# VoiceRecognition_Team3.net
KiCad netlist of a schematic drawn in EAGLE
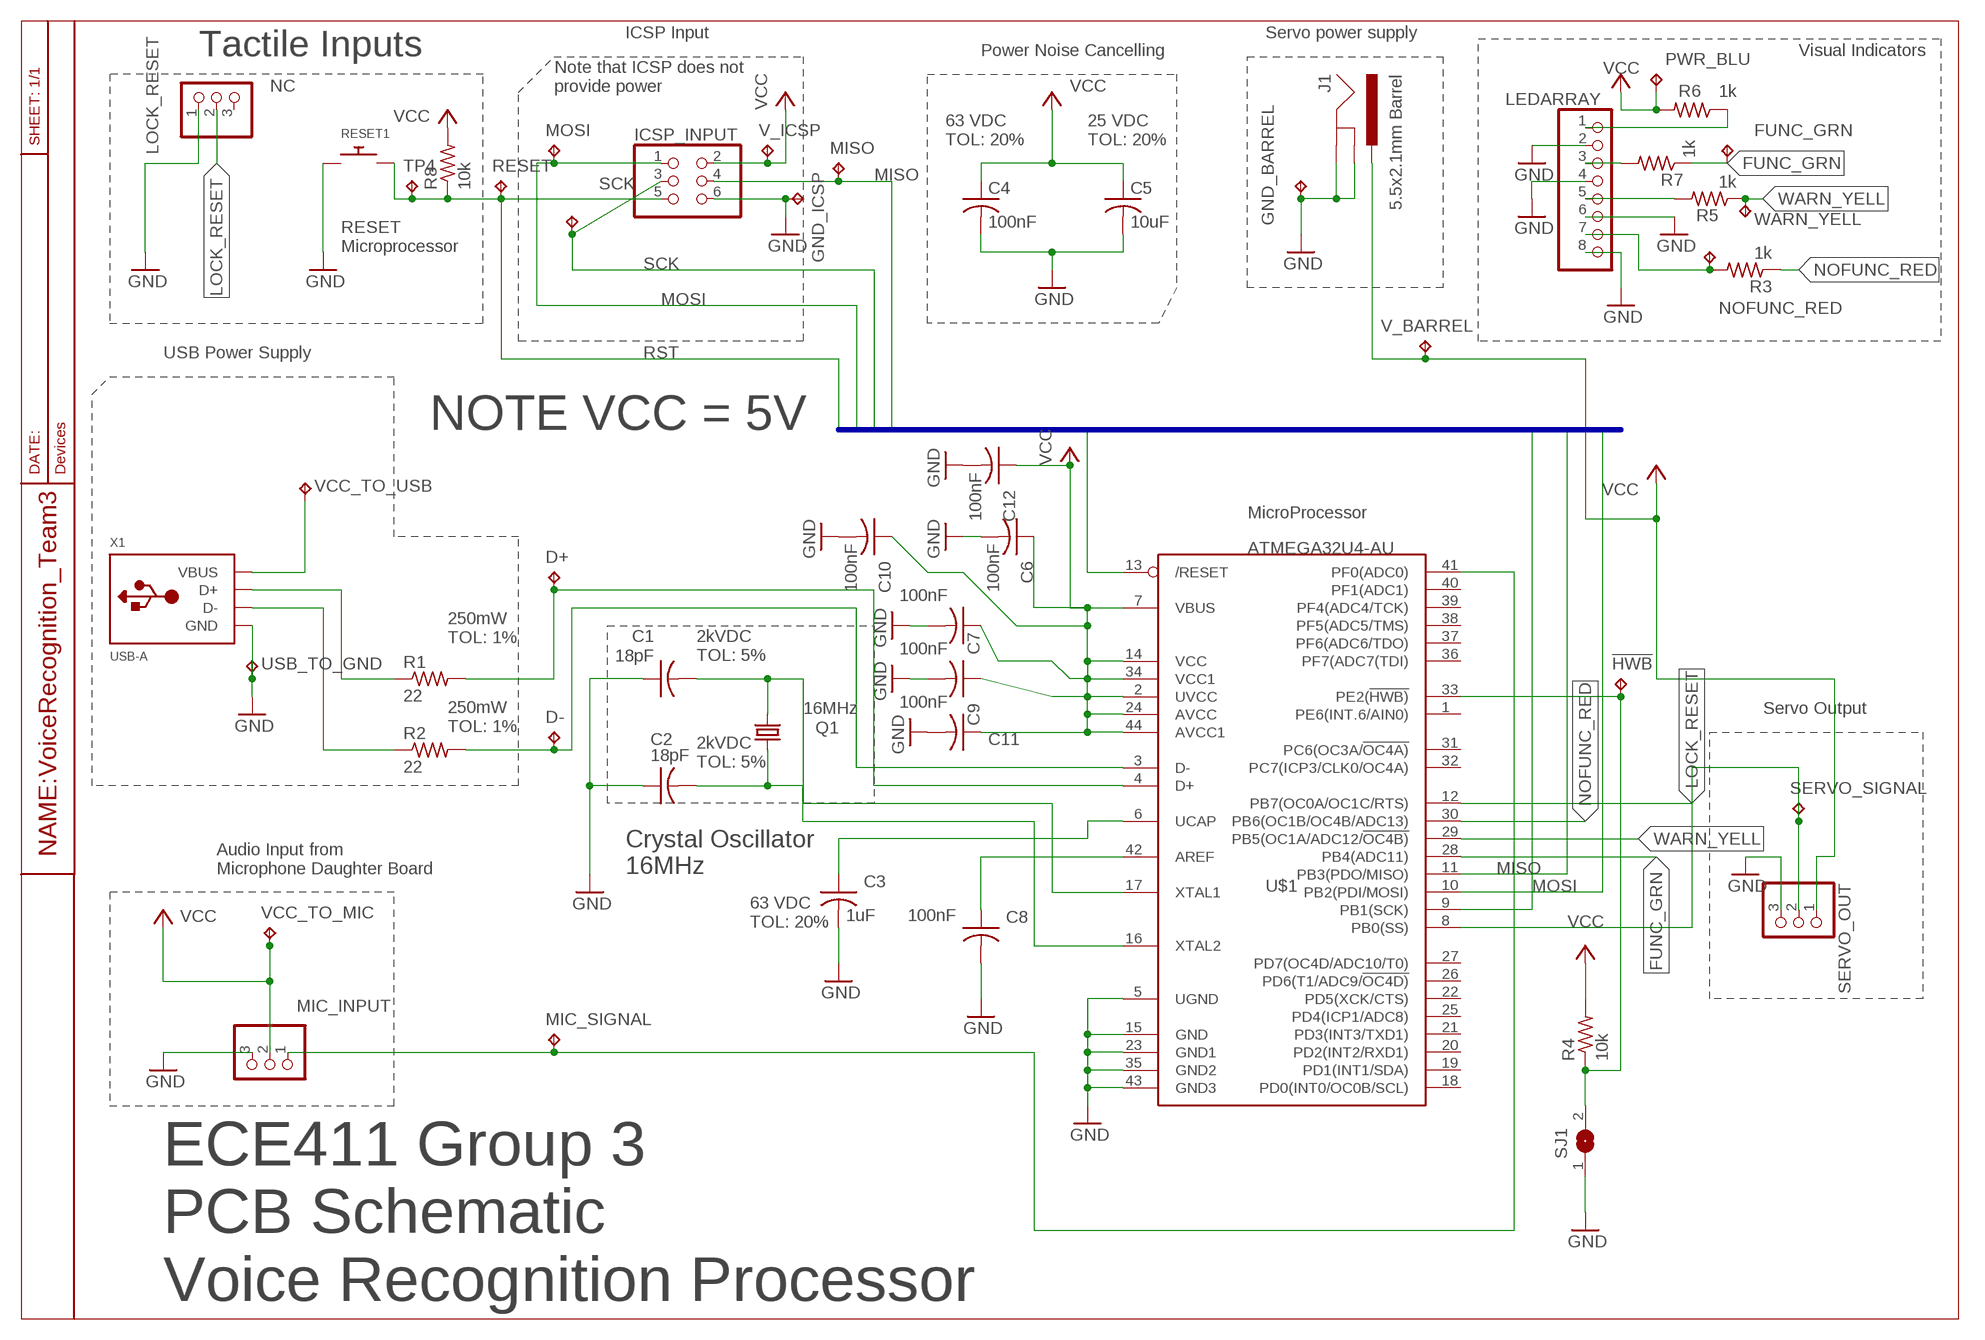
[diagram p0: schematic, sheet 1]

(export (version "E")
  (design (tool "Eeschema 10.0.6"))
  (components
    (comp (ref "!HWB")
      (value "TPTP15SQ")
      (footprint "eagle-import:TP15SQ")
      (libsource (lib "eagle-import") (part "TPTP15SQ"))
    )
    (comp (ref "C1")
      (value "18pF")
      (footprint "eagle-import:C1206")
      (libsource (lib "eagle-import") (part "C-USC1206"))
    )
    (comp (ref "C2")
      (value "18pF")
      (footprint "eagle-import:C1206")
      (libsource (lib "eagle-import") (part "C-USC1206"))
    )
    (comp (ref "C3")
      (value "1uF")
      (footprint "eagle-import:C1206")
      (libsource (lib "eagle-import") (part "C-USC1206"))
    )
    (comp (ref "C4")
      (value "100nF")
      (footprint "eagle-import:C1206")
      (libsource (lib "eagle-import") (part "C-USC1206"))
    )
    (comp (ref "C5")
      (value "10uF")
      (footprint "eagle-import:C1206")
      (libsource (lib "eagle-import") (part "C-USC1206"))
    )
    (comp (ref "C6")
      (value "100nF")
      (footprint "eagle-import:C1206")
      (libsource (lib "eagle-import") (part "C-USC1206"))
    )
    (comp (ref "C7")
      (value "100nF")
      (footprint "eagle-import:C1206")
      (libsource (lib "eagle-import") (part "C-USC1206"))
    )
    (comp (ref "C8")
      (value "100nF")
      (footprint "eagle-import:C1206")
      (libsource (lib "eagle-import") (part "C-USC1206"))
    )
    (comp (ref "C9")
      (value "100nF")
      (footprint "eagle-import:C1206")
      (libsource (lib "eagle-import") (part "C-USC1206"))
    )
    (comp (ref "C10")
      (value "100nF")
      (footprint "eagle-import:C1206")
      (libsource (lib "eagle-import") (part "C-USC1206"))
    )
    (comp (ref "C11")
      (value "100nF")
      (footprint "eagle-import:C1206")
      (libsource (lib "eagle-import") (part "C-USC1206"))
    )
    (comp (ref "C12")
      (value "100nF")
      (footprint "eagle-import:C1206")
      (libsource (lib "eagle-import") (part "C-USC1206"))
    )
    (comp (ref "D+")
      (value "TPTP15SQ")
      (footprint "eagle-import:TP15SQ")
      (libsource (lib "eagle-import") (part "TPTP15SQ"))
    )
    (comp (ref "D-")
      (value "TPTP15SQ")
      (footprint "eagle-import:TP15SQ")
      (libsource (lib "eagle-import") (part "TPTP15SQ"))
    )
    (comp (ref "FUNC_GRN")
      (value "TPTP15SQ")
      (footprint "eagle-import:TP15SQ")
      (libsource (lib "eagle-import") (part "TPTP15SQ"))
    )
    (comp (ref "GND_BARREL")
      (value "TPTP15SQ")
      (footprint "eagle-import:TP15SQ")
      (libsource (lib "eagle-import") (part "TPTP15SQ"))
    )
    (comp (ref "GND_ICSP")
      (value "TPTP15SQ")
      (footprint "eagle-import:TP15SQ")
      (libsource (lib "eagle-import") (part "TPTP15SQ"))
    )
    (comp (ref "ICSP_INPUT")
      (value "PINHD-2X3")
      (footprint "eagle-import:2X03")
      (libsource (lib "eagle-import") (part "PINHD-2X3"))
    )
    (comp (ref "J1")
      (value "5.5x2.1mm Barrel")
      (footprint "eagle-import:POWER_JACK_SMD")
      (libsource (lib "eagle-import") (part "POWER_JACKSMD"))
    )
    (comp (ref "LEDARRAY")
      (value "PINHD-1X8BIG")
      (footprint "eagle-import:1X08-BIG")
      (libsource (lib "eagle-import") (part "PINHD-1X8BIG"))
    )
    (comp (ref "LOCK_RESET")
      (value "PINHD-1X3")
      (footprint "eagle-import:1X03")
      (libsource (lib "eagle-import") (part "PINHD-1X3"))
    )
    (comp (ref "MIC_INPUT")
      (value "PINHD-1X3")
      (footprint "eagle-import:1X03")
      (libsource (lib "eagle-import") (part "pinhead_325_PINHD-1X3"))
    )
    (comp (ref "MIC_SIGNAL")
      (value "TPTP15SQ")
      (footprint "eagle-import:TP15SQ")
      (libsource (lib "eagle-import") (part "TPTP15SQ"))
    )
    (comp (ref "MISO")
      (value "TPTP15SQ")
      (footprint "eagle-import:TP15SQ")
      (libsource (lib "eagle-import") (part "TPTP15SQ"))
    )
    (comp (ref "MOSI")
      (value "TPTP15SQ")
      (footprint "eagle-import:TP15SQ")
      (libsource (lib "eagle-import") (part "TPTP15SQ"))
    )
    (comp (ref "NOFUNC_RED")
      (value "TPTP15SQ")
      (footprint "eagle-import:TP15SQ")
      (libsource (lib "eagle-import") (part "TPTP15SQ"))
    )
    (comp (ref "PWR_BLU")
      (value "TPTP15SQ")
      (footprint "eagle-import:TP15SQ")
      (libsource (lib "eagle-import") (part "TPTP15SQ"))
    )
    (comp (ref "Q1")
      (value "16MHz")
      (footprint "eagle-import:CTS406")
      (libsource (lib "eagle-import") (part "CRYSTALCTS406"))
    )
    (comp (ref "R1")
      (value "22")
      (footprint "eagle-import:M1206")
      (libsource (lib "eagle-import") (part "R-US_M1206"))
    )
    (comp (ref "R2")
      (value "22")
      (footprint "eagle-import:M1206")
      (libsource (lib "eagle-import") (part "R-US_M1206"))
    )
    (comp (ref "R3")
      (value "1k")
      (footprint "eagle-import:M1206")
      (libsource (lib "eagle-import") (part "R-US_M1206"))
    )
    (comp (ref "R4")
      (value "10k")
      (footprint "eagle-import:M1206")
      (libsource (lib "eagle-import") (part "R-US_M1206"))
    )
    (comp (ref "R5")
      (value "1k")
      (footprint "eagle-import:M1206")
      (libsource (lib "eagle-import") (part "R-US_M1206"))
    )
    (comp (ref "R6")
      (value "1k")
      (footprint "eagle-import:M1206")
      (libsource (lib "eagle-import") (part "R-US_M1206"))
    )
    (comp (ref "R7")
      (value "1k")
      (footprint "eagle-import:M1206")
      (libsource (lib "eagle-import") (part "R-US_M1206"))
    )
    (comp (ref "R8")
      (value "10k")
      (footprint "eagle-import:M1206")
      (libsource (lib "eagle-import") (part "R-US_M1206"))
    )
    (comp (ref "RESET")
      (value "TPTP15SQ")
      (footprint "eagle-import:TP15SQ")
      (libsource (lib "eagle-import") (part "TPTP15SQ"))
    )
    (comp (ref "RESET1")
      (value "SWITCH_PUSHBUTTONC&K_KSS")
      (footprint "eagle-import:BTN_CK_KSS")
      (libsource (lib "eagle-import") (part "SWITCH_PUSHBUTTONC&K_KSS"))
    )
    (comp (ref "SCK")
      (value "TPTP15SQ")
      (footprint "eagle-import:TP15SQ")
      (libsource (lib "eagle-import") (part "TPTP15SQ"))
    )
    (comp (ref "SERVO_OUT")
      (value "PINHD-1X3")
      (footprint "eagle-import:1X03")
      (libsource (lib "eagle-import") (part "pinhead_325_PINHD-1X3"))
    )
    (comp (ref "SERVO_SIGNAL")
      (value "TPTP15SQ")
      (footprint "eagle-import:TP15SQ")
      (libsource (lib "eagle-import") (part "TPTP15SQ"))
    )
    (comp (ref "SJ1")
      (value "SJW")
      (footprint "eagle-import:SJW")
      (libsource (lib "eagle-import") (part "SJW"))
    )
    (comp (ref "TP4")
      (value "TPTP15SQ")
      (footprint "eagle-import:TP15SQ")
      (libsource (lib "eagle-import") (part "TPTP15SQ"))
    )
    (comp (ref "U$1")
      (value "ATMEGA32U4-AU")
      (footprint "eagle-import:TQFP44")
      (libsource (lib "eagle-import") (part "ATMEGA32U4-AU"))
    )
    (comp (ref "USB_TO_GND")
      (value "TPTP15SQ")
      (footprint "eagle-import:TP15SQ")
      (libsource (lib "eagle-import") (part "TPTP15SQ"))
    )
    (comp (ref "VCC_TO_MIC")
      (value "TPTP15SQ")
      (footprint "eagle-import:TP15SQ")
      (libsource (lib "eagle-import") (part "TPTP15SQ"))
    )
    (comp (ref "VCC_TO_USB")
      (value "TPTP15SQ")
      (footprint "eagle-import:TP15SQ")
      (libsource (lib "eagle-import") (part "TPTP15SQ"))
    )
    (comp (ref "V_BARREL")
      (value "TPTP15SQ")
      (footprint "eagle-import:TP15SQ")
      (libsource (lib "eagle-import") (part "TPTP15SQ"))
    )
    (comp (ref "V_ICSP")
      (value "TPTP15SQ")
      (footprint "eagle-import:TP15SQ")
      (libsource (lib "eagle-import") (part "TPTP15SQ"))
    )
    (comp (ref "WARN_YELL")
      (value "TPTP15SQ")
      (footprint "eagle-import:TP15SQ")
      (libsource (lib "eagle-import") (part "TPTP15SQ"))
    )
    (comp (ref "X1")
      (value "USB-A")
      (footprint "eagle-import:MOLEX_480371000")
      (libsource (lib "eagle-import") (part "USB-A"))
    )
  )
  (nets
    (net (code "1") (name "/MISO") (class "Default")
      (node (ref "ICSP_INPUT") (pin "4") (pinfunction "4_4") (pintype "passive"))
      (node (ref "MISO") (pin "TP") (pinfunction "TP_TP") (pintype "input"))
      (node (ref "U$1") (pin "11") (pinfunction "PB3(PDO/MISO)_11") (pintype "bidirectional"))
    )
    (net (code "2") (name "/MOSI") (class "Default")
      (node (ref "ICSP_INPUT") (pin "1") (pinfunction "1_1") (pintype "passive"))
      (node (ref "MOSI") (pin "TP") (pinfunction "TP_TP") (pintype "input"))
      (node (ref "U$1") (pin "10") (pinfunction "PB2(PDI/MOSI)_10") (pintype "bidirectional"))
    )
    (net (code "3") (name "/RST") (class "Default")
      (node (ref "ICSP_INPUT") (pin "5") (pinfunction "5_5") (pintype "passive"))
      (node (ref "R8") (pin "1") (pinfunction "1_1") (pintype "passive"))
      (node (ref "RESET") (pin "TP") (pinfunction "TP_TP") (pintype "input"))
      (node (ref "RESET1") (pin "P$2") (pinfunction "P$2_P$2") (pintype "passive"))
      (node (ref "TP4") (pin "TP") (pinfunction "TP_TP") (pintype "input"))
      (node (ref "U$1") (pin "13") (pinfunction "/RESET_13") (pintype "bidirectional"))
    )
    (net (code "4") (name "/SCK") (class "Default")
      (node (ref "ICSP_INPUT") (pin "3") (pinfunction "3_3") (pintype "passive"))
      (node (ref "SCK") (pin "TP") (pinfunction "TP_TP") (pintype "input"))
      (node (ref "U$1") (pin "9") (pinfunction "PB1(SCK)_9") (pintype "bidirectional"))
    )
    (net (code "5") (name "FUNC_GRN") (class "Default")
      (node (ref "FUNC_GRN") (pin "TP") (pinfunction "TP_TP") (pintype "input"))
      (node (ref "LEDARRAY") (pin "3") (pinfunction "3_3") (pintype "passive"))
      (node (ref "R7") (pin "1") (pinfunction "1_1") (pintype "passive"))
      (node (ref "R7") (pin "2") (pinfunction "2_2") (pintype "passive"))
      (node (ref "U$1") (pin "28") (pinfunction "PB4(ADC11)_28") (pintype "bidirectional"))
    )
    (net (code "6") (name "GND") (class "Default")
      (node (ref "C1") (pin "1") (pinfunction "1_1") (pintype "passive"))
      (node (ref "C10") (pin "2") (pinfunction "2_2") (pintype "passive"))
      (node (ref "C11") (pin "2") (pinfunction "2_2") (pintype "passive"))
      (node (ref "C12") (pin "2") (pinfunction "2_2") (pintype "passive"))
      (node (ref "C2") (pin "1") (pinfunction "1_1") (pintype "passive"))
      (node (ref "C3") (pin "2") (pinfunction "2_2") (pintype "passive"))
      (node (ref "C4") (pin "2") (pinfunction "2_2") (pintype "passive"))
      (node (ref "C5") (pin "2") (pinfunction "2_2") (pintype "passive"))
      (node (ref "C6") (pin "2") (pinfunction "2_2") (pintype "passive"))
      (node (ref "C7") (pin "2") (pinfunction "2_2") (pintype "passive"))
      (node (ref "C8") (pin "2") (pinfunction "2_2") (pintype "passive"))
      (node (ref "C9") (pin "2") (pinfunction "2_2") (pintype "passive"))
      (node (ref "GND_BARREL") (pin "TP") (pinfunction "TP_TP") (pintype "input"))
      (node (ref "GND_ICSP") (pin "TP") (pinfunction "TP_TP") (pintype "input"))
      (node (ref "ICSP_INPUT") (pin "6") (pinfunction "6_6") (pintype "passive"))
      (node (ref "J1") (pin "GND") (pinfunction "GNDBREAK_GND") (pintype "bidirectional"))
      (node (ref "J1") (pin "P$4") (pinfunction "GND_P$4") (pintype "bidirectional"))
      (node (ref "LEDARRAY") (pin "2") (pinfunction "2_2") (pintype "passive"))
      (node (ref "LEDARRAY") (pin "4") (pinfunction "4_4") (pintype "passive"))
      (node (ref "LEDARRAY") (pin "6") (pinfunction "6_6") (pintype "passive"))
      (node (ref "LEDARRAY") (pin "8") (pinfunction "8_8") (pintype "passive"))
      (node (ref "LOCK_RESET") (pin "1") (pinfunction "1_1") (pintype "passive"))
      (node (ref "MIC_INPUT") (pin "3") (pinfunction "3_3") (pintype "passive"))
      (node (ref "RESET1") (pin "P$1") (pinfunction "P$1_P$1") (pintype "passive"))
      (node (ref "SERVO_OUT") (pin "3") (pinfunction "3_3") (pintype "passive"))
      (node (ref "SJ1") (pin "1") (pinfunction "1_1") (pintype "passive"))
      (node (ref "U$1") (pin "15") (pinfunction "GND_15") (pintype "bidirectional"))
      (node (ref "U$1") (pin "23") (pinfunction "GND1_23") (pintype "bidirectional"))
      (node (ref "U$1") (pin "35") (pinfunction "GND2_35") (pintype "bidirectional"))
      (node (ref "U$1") (pin "43") (pinfunction "GND3_43") (pintype "bidirectional"))
      (node (ref "U$1") (pin "5") (pinfunction "UGND_5") (pintype "bidirectional"))
      (node (ref "USB_TO_GND") (pin "TP") (pinfunction "TP_TP") (pintype "input"))
      (node (ref "X1") (pin "4") (pinfunction "GND_4") (pintype "power_in"))
    )
    (net (code "7") (name "LOCK_RESET") (class "Default")
      (node (ref "LOCK_RESET") (pin "2") (pinfunction "2_2") (pintype "passive"))
      (node (ref "U$1") (pin "12") (pinfunction "PB7(OC0A/OC1C/RTS)_12") (pintype "bidirectional"))
    )
    (net (code "8") (name "NOFUNC_RED") (class "Default")
      (node (ref "R3") (pin "1") (pinfunction "1_1") (pintype "passive"))
      (node (ref "U$1") (pin "30") (pinfunction "PB6(OC1B/OC4B/ADC13)_30") (pintype "bidirectional"))
    )
    (net (code "9") (name "Net-(LEDARRAY-Pad1)") (class "Default")
      (node (ref "LEDARRAY") (pin "1") (pinfunction "1_1") (pintype "passive"))
      (node (ref "R6") (pin "1") (pinfunction "1_1") (pintype "passive"))
    )
    (net (code "10") (name "Net-(LEDARRAY-Pad5)") (class "Default")
      (node (ref "LEDARRAY") (pin "5") (pinfunction "5_5") (pintype "passive"))
      (node (ref "R5") (pin "2") (pinfunction "2_2") (pintype "passive"))
    )
    (net (code "11") (name "Net-(LEDARRAY-Pad7)") (class "Default")
      (node (ref "LEDARRAY") (pin "7") (pinfunction "7_7") (pintype "passive"))
      (node (ref "NOFUNC_RED") (pin "TP") (pinfunction "TP_TP") (pintype "input"))
      (node (ref "R3") (pin "2") (pinfunction "2_2") (pintype "passive"))
    )
    (net (code "12") (name "Net-(Q1-2)") (class "Default")
      (node (ref "C1") (pin "2") (pinfunction "2_2") (pintype "passive"))
      (node (ref "Q1") (pin "3") (pinfunction "2_3") (pintype "passive"))
      (node (ref "U$1") (pin "17") (pinfunction "XTAL1_17") (pintype "bidirectional"))
    )
    (net (code "13") (name "Net-(U$1-AREF)") (class "Default")
      (node (ref "C8") (pin "1") (pinfunction "1_1") (pintype "passive"))
      (node (ref "U$1") (pin "42") (pinfunction "AREF_42") (pintype "bidirectional"))
    )
    (net (code "14") (name "Net-(U$1-D+)") (class "Default")
      (node (ref "D+") (pin "TP") (pinfunction "TP_TP") (pintype "input"))
      (node (ref "R1") (pin "2") (pinfunction "2_2") (pintype "passive"))
      (node (ref "U$1") (pin "4") (pinfunction "D+_4") (pintype "bidirectional"))
    )
    (net (code "15") (name "Net-(U$1-D-)") (class "Default")
      (node (ref "D-") (pin "TP") (pinfunction "TP_TP") (pintype "input"))
      (node (ref "R2") (pin "2") (pinfunction "2_2") (pintype "passive"))
      (node (ref "U$1") (pin "3") (pinfunction "D-_3") (pintype "bidirectional"))
    )
    (net (code "16") (name "Net-(U$1-PB0(SS))") (class "Default")
      (node (ref "SERVO_OUT") (pin "2") (pinfunction "2_2") (pintype "passive"))
      (node (ref "SERVO_SIGNAL") (pin "TP") (pinfunction "TP_TP") (pintype "input"))
      (node (ref "U$1") (pin "8") (pinfunction "PB0(SS)_8") (pintype "bidirectional"))
    )
    (net (code "17") (name "Net-(U$1-PE2(~{HWB}))") (class "Default")
      (node (ref "!HWB") (pin "TP") (pinfunction "TP_TP") (pintype "input"))
      (node (ref "R4") (pin "1") (pinfunction "1_1") (pintype "passive"))
      (node (ref "SJ1") (pin "2") (pinfunction "2_2") (pintype "passive"))
      (node (ref "U$1") (pin "33") (pinfunction "PE2(~{HWB})_33") (pintype "bidirectional"))
    )
    (net (code "18") (name "Net-(U$1-PF0(ADC0))") (class "Default")
      (node (ref "MIC_INPUT") (pin "1") (pinfunction "1_1") (pintype "passive"))
      (node (ref "MIC_SIGNAL") (pin "TP") (pinfunction "TP_TP") (pintype "input"))
      (node (ref "U$1") (pin "41") (pinfunction "PF0(ADC0)_41") (pintype "bidirectional"))
    )
    (net (code "19") (name "Net-(U$1-UCAP)") (class "Default")
      (node (ref "C3") (pin "1") (pinfunction "1_1") (pintype "passive"))
      (node (ref "U$1") (pin "6") (pinfunction "UCAP_6") (pintype "bidirectional"))
    )
    (net (code "20") (name "Net-(U$1-XTAL2)") (class "Default")
      (node (ref "C2") (pin "2") (pinfunction "2_2") (pintype "passive"))
      (node (ref "Q1") (pin "1") (pinfunction "1_1") (pintype "passive"))
      (node (ref "U$1") (pin "16") (pinfunction "XTAL2_16") (pintype "bidirectional"))
    )
    (net (code "21") (name "Net-(X1-D+)") (class "Default")
      (node (ref "R1") (pin "1") (pinfunction "1_1") (pintype "passive"))
      (node (ref "X1") (pin "3") (pinfunction "D+_3") (pintype "bidirectional"))
    )
    (net (code "22") (name "Net-(X1-D-)") (class "Default")
      (node (ref "R2") (pin "1") (pinfunction "1_1") (pintype "passive"))
      (node (ref "X1") (pin "2") (pinfunction "D-_2") (pintype "bidirectional"))
    )
    (net (code "23") (name "Net-(X1-VBUS)") (class "Default")
      (node (ref "VCC_TO_USB") (pin "TP") (pinfunction "TP_TP") (pintype "input"))
      (node (ref "X1") (pin "1") (pinfunction "VBUS_1") (pintype "power_in"))
    )
    (net (code "24") (name "VCC") (class "Default")
      (node (ref "C10") (pin "1") (pinfunction "1_1") (pintype "passive"))
      (node (ref "C11") (pin "1") (pinfunction "1_1") (pintype "passive"))
      (node (ref "C12") (pin "1") (pinfunction "1_1") (pintype "passive"))
      (node (ref "C4") (pin "1") (pinfunction "1_1") (pintype "passive"))
      (node (ref "C5") (pin "1") (pinfunction "1_1") (pintype "passive"))
      (node (ref "C6") (pin "1") (pinfunction "1_1") (pintype "passive"))
      (node (ref "C7") (pin "1") (pinfunction "1_1") (pintype "passive"))
      (node (ref "C9") (pin "1") (pinfunction "1_1") (pintype "passive"))
      (node (ref "ICSP_INPUT") (pin "2") (pinfunction "2_2") (pintype "passive"))
      (node (ref "J1") (pin "VIN0") (pinfunction "PWR_VIN0") (pintype "bidirectional"))
      (node (ref "MIC_INPUT") (pin "2") (pinfunction "2_2") (pintype "passive"))
      (node (ref "PWR_BLU") (pin "TP") (pinfunction "TP_TP") (pintype "input"))
      (node (ref "R4") (pin "2") (pinfunction "2_2") (pintype "passive"))
      (node (ref "R6") (pin "2") (pinfunction "2_2") (pintype "passive"))
      (node (ref "R8") (pin "2") (pinfunction "2_2") (pintype "passive"))
      (node (ref "SERVO_OUT") (pin "1") (pinfunction "1_1") (pintype "passive"))
      (node (ref "U$1") (pin "14") (pinfunction "VCC_14") (pintype "bidirectional"))
      (node (ref "U$1") (pin "2") (pinfunction "UVCC_2") (pintype "bidirectional"))
      (node (ref "U$1") (pin "24") (pinfunction "AVCC_24") (pintype "bidirectional"))
      (node (ref "U$1") (pin "34") (pinfunction "VCC1_34") (pintype "bidirectional"))
      (node (ref "U$1") (pin "44") (pinfunction "AVCC1_44") (pintype "bidirectional"))
      (node (ref "U$1") (pin "7") (pinfunction "VBUS_7") (pintype "bidirectional"))
      (node (ref "VCC_TO_MIC") (pin "TP") (pinfunction "TP_TP") (pintype "input"))
      (node (ref "V_BARREL") (pin "TP") (pinfunction "TP_TP") (pintype "input"))
      (node (ref "V_ICSP") (pin "TP") (pinfunction "TP_TP") (pintype "input"))
    )
    (net (code "25") (name "WARN_YELL") (class "Default")
      (node (ref "R5") (pin "1") (pinfunction "1_1") (pintype "passive"))
      (node (ref "U$1") (pin "29") (pinfunction "PB5(OC1A/ADC12/~{OC4B})_29") (pintype "bidirectional"))
      (node (ref "WARN_YELL") (pin "TP") (pinfunction "TP_TP") (pintype "input"))
    )
    (net (code "26") (name "unconnected-(LOCK_RESET-Pad3)") (class "Default")
      (node (ref "LOCK_RESET") (pin "3") (pinfunction "3_3") (pintype "passive"))
    )
    (net (code "27") (name "unconnected-(U$1-PC6(OC3A{slash}~{OC4A})-Pad31)") (class "Default")
      (node (ref "U$1") (pin "31") (pinfunction "PC6(OC3A/~{OC4A})_31") (pintype "bidirectional"))
    )
    (net (code "28") (name "unconnected-(U$1-PC7(ICP3{slash}CLK0{slash}OC4A)-Pad32)") (class "Default")
      (node (ref "U$1") (pin "32") (pinfunction "PC7(ICP3/CLK0/OC4A)_32") (pintype "bidirectional"))
    )
    (net (code "29") (name "unconnected-(U$1-PD0(INT0{slash}OC0B{slash}SCL)-Pad18)") (class "Default")
      (node (ref "U$1") (pin "18") (pinfunction "PD0(INT0/OC0B/SCL)_18") (pintype "bidirectional"))
    )
    (net (code "30") (name "unconnected-(U$1-PD1(INT1{slash}SDA)-Pad19)") (class "Default")
      (node (ref "U$1") (pin "19") (pinfunction "PD1(INT1/SDA)_19") (pintype "bidirectional"))
    )
    (net (code "31") (name "unconnected-(U$1-PD2(INT2{slash}RXD1)-Pad20)") (class "Default")
      (node (ref "U$1") (pin "20") (pinfunction "PD2(INT2/RXD1)_20") (pintype "bidirectional"))
    )
    (net (code "32") (name "unconnected-(U$1-PD3(INT3{slash}TXD1)-Pad21)") (class "Default")
      (node (ref "U$1") (pin "21") (pinfunction "PD3(INT3/TXD1)_21") (pintype "bidirectional"))
    )
    (net (code "33") (name "unconnected-(U$1-PD4(ICP1{slash}ADC8)-Pad25)") (class "Default")
      (node (ref "U$1") (pin "25") (pinfunction "PD4(ICP1/ADC8)_25") (pintype "bidirectional"))
    )
    (net (code "34") (name "unconnected-(U$1-PD5(XCK{slash}CTS)-Pad22)") (class "Default")
      (node (ref "U$1") (pin "22") (pinfunction "PD5(XCK/CTS)_22") (pintype "bidirectional"))
    )
    (net (code "35") (name "unconnected-(U$1-PD6(T1{slash}ADC9{slash}~{OC4D})-Pad26)") (class "Default")
      (node (ref "U$1") (pin "26") (pinfunction "PD6(T1/ADC9/~{OC4D})_26") (pintype "bidirectional"))
    )
    (net (code "36") (name "unconnected-(U$1-PD7(OC4D{slash}ADC10{slash}T0)-Pad27)") (class "Default")
      (node (ref "U$1") (pin "27") (pinfunction "PD7(OC4D/ADC10/T0)_27") (pintype "bidirectional"))
    )
    (net (code "37") (name "unconnected-(U$1-PE6(INT.6{slash}AIN0)-Pad1)") (class "Default")
      (node (ref "U$1") (pin "1") (pinfunction "PE6(INT.6/AIN0)_1") (pintype "bidirectional"))
    )
    (net (code "38") (name "unconnected-(U$1-PF1(ADC1)-Pad40)") (class "Default")
      (node (ref "U$1") (pin "40") (pinfunction "PF1(ADC1)_40") (pintype "bidirectional"))
    )
    (net (code "39") (name "unconnected-(U$1-PF4(ADC4{slash}TCK)-Pad39)") (class "Default")
      (node (ref "U$1") (pin "39") (pinfunction "PF4(ADC4/TCK)_39") (pintype "bidirectional"))
    )
    (net (code "40") (name "unconnected-(U$1-PF5(ADC5{slash}TMS)-Pad38)") (class "Default")
      (node (ref "U$1") (pin "38") (pinfunction "PF5(ADC5/TMS)_38") (pintype "bidirectional"))
    )
    (net (code "41") (name "unconnected-(U$1-PF6(ADC6{slash}TDO)-Pad37)") (class "Default")
      (node (ref "U$1") (pin "37") (pinfunction "PF6(ADC6/TDO)_37") (pintype "bidirectional"))
    )
    (net (code "42") (name "unconnected-(U$1-PF7(ADC7(TDI)-Pad36)") (class "Default")
      (node (ref "U$1") (pin "36") (pinfunction "PF7(ADC7(TDI)_36") (pintype "bidirectional"))
    )
  )
)
